# SCH_555-Circuit_2026-01-03.net
KiCad netlist of a schematic drawn in EasyEDA
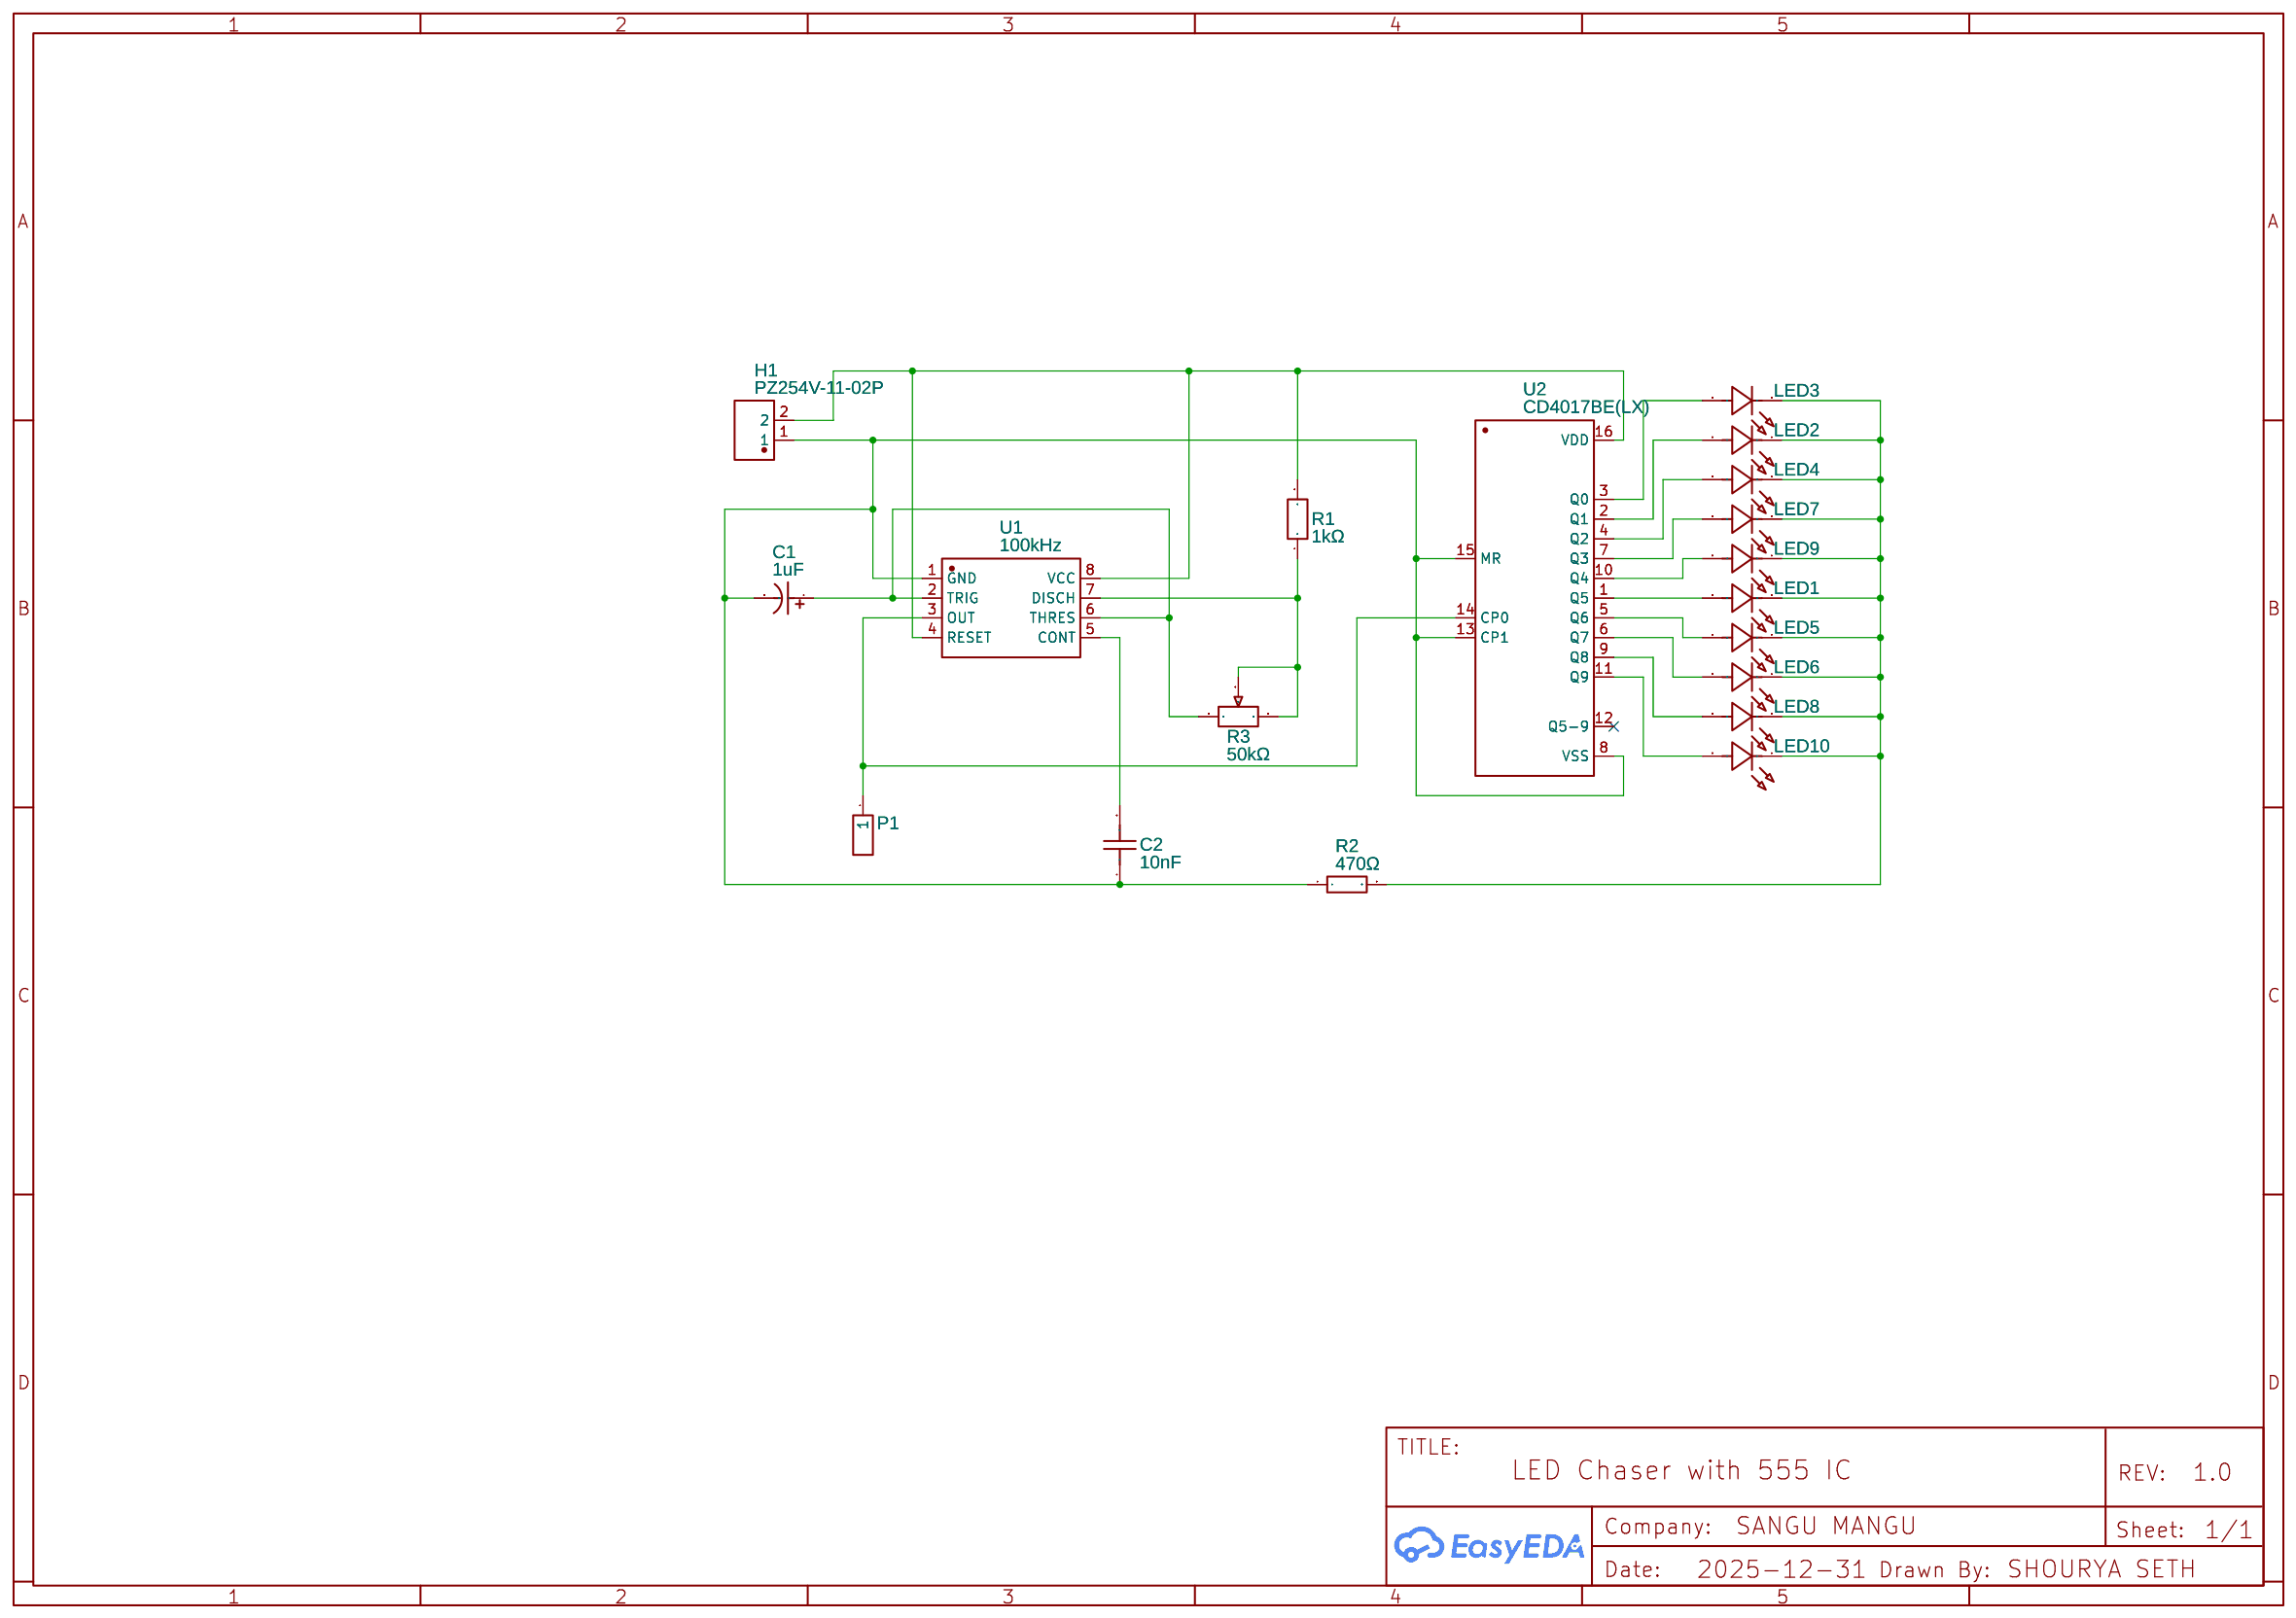
[diagram p0: schematic sheet]

(export (version "E")
  (design (tool "Eeschema 10.0.6"))
  (components
    (comp (ref "C1")
      (value "1uF")
      (fields (field (name "Manufacturer Part") "KF010M050C110A") (field (name "Manufacturer") "CapXon(丰宾)"))
      (libsource (lib "") (part "KF010M050C110A"))
    )
    (comp (ref "C2")
      (value "10nF")
      (fields (field (name "Manufacturer Part") "N09F1B103MN0B0S0N0") (field (name "Manufacturer") "STE(松田)"))
      (libsource (lib "") (part "N09F1B103MN0B0S0N0"))
    )
    (comp (ref "H1")
      (value "PZ254V-11-02P")
      (fields (field (name "Manufacturer") "XFCN(兴飞)"))
      (libsource (lib "") (part "PZ254V-11-02P"))
    )
    (comp (ref "LED1")
      (value "XL-502UWC")
      (fields (field (name "Manufacturer") "XINGLIGHT(成兴光)"))
      (libsource (lib "") (part "XL-502UWC"))
    )
    (comp (ref "LED2")
      (value "XL-502UWC")
      (fields (field (name "Manufacturer") "XINGLIGHT(成兴光)"))
      (libsource (lib "") (part "XL-502UWC"))
    )
    (comp (ref "LED3")
      (value "XL-502UWC")
      (fields (field (name "Manufacturer") "XINGLIGHT(成兴光)"))
      (libsource (lib "") (part "XL-502UWC"))
    )
    (comp (ref "LED4")
      (value "XL-502UWC")
      (fields (field (name "Manufacturer") "XINGLIGHT(成兴光)"))
      (libsource (lib "") (part "XL-502UWC"))
    )
    (comp (ref "LED5")
      (value "XL-502UWC")
      (fields (field (name "Manufacturer") "XINGLIGHT(成兴光)"))
      (libsource (lib "") (part "XL-502UWC"))
    )
    (comp (ref "LED6")
      (value "XL-502UWC")
      (fields (field (name "Manufacturer") "XINGLIGHT(成兴光)"))
      (libsource (lib "") (part "XL-502UWC"))
    )
    (comp (ref "LED7")
      (value "XL-502UWC")
      (fields (field (name "Manufacturer") "XINGLIGHT(成兴光)"))
      (libsource (lib "") (part "XL-502UWC"))
    )
    (comp (ref "LED8")
      (value "XL-502UWC")
      (fields (field (name "Manufacturer") "XINGLIGHT(成兴光)"))
      (libsource (lib "") (part "XL-502UWC"))
    )
    (comp (ref "LED9")
      (value "XL-502UWC")
      (fields (field (name "Manufacturer") "XINGLIGHT(成兴光)"))
      (libsource (lib "") (part "XL-502UWC"))
    )
    (comp (ref "LED10")
      (value "XL-502UWC")
      (fields (field (name "Manufacturer") "XINGLIGHT(成兴光)"))
      (libsource (lib "") (part "XL-502UWC"))
    )
    (comp (ref "P1")
      (value "Header-Male-2.54_1x1")
      (fields (field (name "Manufacturer Part") "2.54-1*1P针") (field (name "Manufacturer") "BOOMELE(博穆精密)"))
      (libsource (lib "") (part "Header-Male-2.54_1x1"))
    )
    (comp (ref "R1")
      (value "1kΩ")
      (fields (field (name "Manufacturer Part") "MF1/4W-1KΩ±1%T52") (field (name "Manufacturer") "华星机电"))
      (libsource (lib "") (part "MF1/4W-1KΩ±1%T52"))
    )
    (comp (ref "R2")
      (value "470Ω")
      (fields
        (field (name "Manufacturer Part") "MFR0W4F4700A50")
        (field (name "Manufacturer") "UNI-ROYAL(厚声)")
      )
      (libsource (lib "") (part "MFR0W4F4700A50"))
    )
    (comp (ref "R3")
      (value "50kΩ")
      (fields (field (name "Manufacturer Part") "3296X-1-503") (field (name "Manufacturer") "BOCHEN(博晨)"))
      (libsource (lib "") (part "3296X-1-503_C118912"))
    )
    (comp (ref "U1")
      (value "100kHz")
      (fields (field (name "Manufacturer Part") "NE555P") (field (name "Manufacturer") "TI(德州仪器)"))
      (libsource (lib "") (part "NE555P"))
    )
    (comp (ref "U2")
      (value "CD4017BE(LX)")
      (fields (field (name "Manufacturer") "LX(灵星芯微)"))
      (libsource (lib "") (part "CD4017BE(LX)"))
    )
  )
  (nets
    (net (code "1") (name "Net-(LED1-A)") (class "Default")
      (node (ref "LED1") (pin "2") (pinfunction "A_2") (pintype "unspecified"))
      (node (ref "U2") (pin "1") (pinfunction "Q5_1") (pintype "unspecified"))
    )
    (net (code "2") (name "Net-(LED1-K)") (class "Default")
      (node (ref "LED1") (pin "1") (pinfunction "K_1") (pintype "unspecified"))
      (node (ref "LED10") (pin "1") (pinfunction "K_1") (pintype "unspecified"))
      (node (ref "LED2") (pin "1") (pinfunction "K_1") (pintype "unspecified"))
      (node (ref "LED3") (pin "1") (pinfunction "K_1") (pintype "unspecified"))
      (node (ref "LED4") (pin "1") (pinfunction "K_1") (pintype "unspecified"))
      (node (ref "LED5") (pin "1") (pinfunction "K_1") (pintype "unspecified"))
      (node (ref "LED6") (pin "1") (pinfunction "K_1") (pintype "unspecified"))
      (node (ref "LED7") (pin "1") (pinfunction "K_1") (pintype "unspecified"))
      (node (ref "LED8") (pin "1") (pinfunction "K_1") (pintype "unspecified"))
      (node (ref "LED9") (pin "1") (pinfunction "K_1") (pintype "unspecified"))
      (node (ref "R2") (pin "2") (pinfunction "2_2") (pintype "input"))
    )
    (net (code "3") (name "Net-(LED2-A)") (class "Default")
      (node (ref "LED2") (pin "2") (pinfunction "A_2") (pintype "unspecified"))
      (node (ref "U2") (pin "2") (pinfunction "Q1_2") (pintype "unspecified"))
    )
    (net (code "4") (name "Net-(LED3-A)") (class "Default")
      (node (ref "LED3") (pin "2") (pinfunction "A_2") (pintype "unspecified"))
      (node (ref "U2") (pin "3") (pinfunction "Q0_3") (pintype "unspecified"))
    )
    (net (code "5") (name "Net-(LED4-A)") (class "Default")
      (node (ref "LED4") (pin "2") (pinfunction "A_2") (pintype "unspecified"))
      (node (ref "U2") (pin "4") (pinfunction "Q2_4") (pintype "unspecified"))
    )
    (net (code "6") (name "Net-(LED5-A)") (class "Default")
      (node (ref "LED5") (pin "2") (pinfunction "A_2") (pintype "unspecified"))
      (node (ref "U2") (pin "5") (pinfunction "Q6_5") (pintype "unspecified"))
    )
    (net (code "7") (name "Net-(LED6-A)") (class "Default")
      (node (ref "LED6") (pin "2") (pinfunction "A_2") (pintype "unspecified"))
      (node (ref "U2") (pin "6") (pinfunction "Q7_6") (pintype "unspecified"))
    )
    (net (code "8") (name "Net-(LED7-A)") (class "Default")
      (node (ref "LED7") (pin "2") (pinfunction "A_2") (pintype "unspecified"))
      (node (ref "U2") (pin "7") (pinfunction "Q3_7") (pintype "unspecified"))
    )
    (net (code "9") (name "Net-(LED8-A)") (class "Default")
      (node (ref "LED8") (pin "2") (pinfunction "A_2") (pintype "unspecified"))
      (node (ref "U2") (pin "9") (pinfunction "Q8_9") (pintype "unspecified"))
    )
    (net (code "10") (name "Net-(LED9-A)") (class "Default")
      (node (ref "LED9") (pin "2") (pinfunction "A_2") (pintype "unspecified"))
      (node (ref "U2") (pin "10") (pinfunction "Q4_10") (pintype "unspecified"))
    )
    (net (code "11") (name "Net-(LED10-A)") (class "Default")
      (node (ref "LED10") (pin "2") (pinfunction "A_2") (pintype "unspecified"))
      (node (ref "U2") (pin "11") (pinfunction "Q9_11") (pintype "unspecified"))
    )
    (net (code "12") (name "Net-(U1-CONT)") (class "Default")
      (node (ref "C2") (pin "2") (pinfunction "2_2") (pintype "unspecified"))
      (node (ref "U1") (pin "5") (pinfunction "CONT_5") (pintype "unspecified"))
    )
    (net (code "13") (name "Net-(U1-DISCH)") (class "Default")
      (node (ref "R1") (pin "1") (pinfunction "1_1") (pintype "unspecified"))
      (node (ref "R3") (pin "2") (pinfunction "2_2") (pintype "input"))
      (node (ref "R3") (pin "3") (pinfunction "3_3") (pintype "input"))
      (node (ref "U1") (pin "7") (pinfunction "DISCH_7") (pintype "unspecified"))
    )
    (net (code "14") (name "Net-(U1-GND)") (class "Default")
      (node (ref "C1") (pin "2") (pinfunction "2_2") (pintype "input"))
      (node (ref "C2") (pin "1") (pinfunction "1_1") (pintype "unspecified"))
      (node (ref "H1") (pin "1") (pinfunction "1_1") (pintype "unspecified"))
      (node (ref "R2") (pin "1") (pinfunction "1_1") (pintype "input"))
      (node (ref "U1") (pin "1") (pinfunction "GND_1") (pintype "unspecified"))
      (node (ref "U2") (pin "13") (pinfunction "CP1_13") (pintype "unspecified"))
      (node (ref "U2") (pin "15") (pinfunction "MR_15") (pintype "unspecified"))
      (node (ref "U2") (pin "8") (pinfunction "VSS_8") (pintype "unspecified"))
    )
    (net (code "15") (name "Net-(U1-OUT)") (class "Default")
      (node (ref "P1") (pin "1") (pinfunction "1_1") (pintype "input"))
      (node (ref "U1") (pin "3") (pinfunction "OUT_3") (pintype "unspecified"))
      (node (ref "U2") (pin "14") (pinfunction "CP0_14") (pintype "unspecified"))
    )
    (net (code "16") (name "Net-(U1-RESET)") (class "Default")
      (node (ref "H1") (pin "2") (pinfunction "2_2") (pintype "unspecified"))
      (node (ref "R1") (pin "2") (pinfunction "2_2") (pintype "unspecified"))
      (node (ref "U1") (pin "4") (pinfunction "RESET_4") (pintype "unspecified"))
      (node (ref "U1") (pin "8") (pinfunction "VCC_8") (pintype "unspecified"))
      (node (ref "U2") (pin "16") (pinfunction "VDD_16") (pintype "unspecified"))
    )
    (net (code "17") (name "Net-(U1-THRES)") (class "Default")
      (node (ref "C1") (pin "1") (pinfunction "1_1") (pintype "input"))
      (node (ref "R3") (pin "1") (pinfunction "1_1") (pintype "input"))
      (node (ref "U1") (pin "2") (pinfunction "TRIG_2") (pintype "unspecified"))
      (node (ref "U1") (pin "6") (pinfunction "THRES_6") (pintype "unspecified"))
    )
    (net (code "18") (name "unconnected-(U2-Q5-9-Pad12)") (class "Default")
      (node (ref "U2") (pin "12") (pinfunction "Q5-9_12") (pintype "unspecified+no_connect"))
    )
  )
)
